# Current_Sensor.net
KiCad netlist of a schematic drawn in Altium Designer
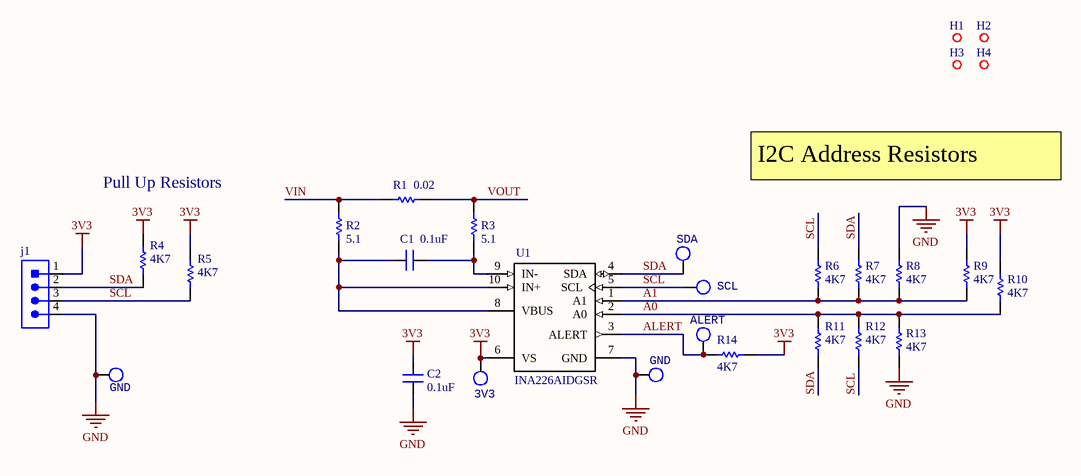
[diagram p0: Current Sensor.SchDoc]

(export (version "E")
  (design (tool "Eeschema 10.0.6"))
  (components
    (comp (ref "C1")
      (value "0.1uF")
      (footprint "CAPC2012X140N")
      (description "CAP CER 0.1UF 50V X7R 0805")
      (fields (field (name "TOLERANCE") "10%") (field (name "Comment") "CAP_0.1uF_50V_0805"))
      (libsource (lib "UWRT_Schematic_Library_2020") (part "CAP_0.1uF_50V_0805"))
    )
    (comp (ref "C2")
      (value "0.1uF")
      (footprint "CAPC2012X140N")
      (description "CAP CER 0.1UF 50V X7R 0805")
      (fields (field (name "TOLERANCE") "10%") (field (name "Comment") "CAP_0.1uF_50V_0805"))
      (libsource (lib "UWRT_Schematic_Library_2020") (part "CAP_0.1uF_50V_0805"))
    )
    (comp (ref "H1")
      (value "MOUNTING_HOLES")
      (footprint "MOUNTING_HOLE")
      (description "6cm x 6cm")
      (libsource (lib "UWRT_Schematic_Library_2020") (part "MOUNTING_HOLES"))
    )
    (comp (ref "H2")
      (value "MOUNTING_HOLES")
      (footprint "MOUNTING_HOLE")
      (description "6cm x 6cm")
      (libsource (lib "UWRT_Schematic_Library_2020") (part "MOUNTING_HOLES"))
    )
    (comp (ref "H3")
      (value "MOUNTING_HOLES")
      (footprint "MOUNTING_HOLE")
      (description "6cm x 6cm")
      (libsource (lib "UWRT_Schematic_Library_2020") (part "MOUNTING_HOLES"))
    )
    (comp (ref "H4")
      (value "MOUNTING_HOLES")
      (footprint "MOUNTING_HOLE")
      (description "6cm x 6cm")
      (libsource (lib "UWRT_Schematic_Library_2020") (part "MOUNTING_HOLES"))
    )
    (comp (ref "j1")
      (value "CON_4M_TERM")
      (footprint "UWRT_Footprint_Library_2020:1935187")
      (description "TERM BLK 4POS SIDE ENTRY 5MM PCB")
      (fields (field (name "VOLTAGE") "300V"))
      (libsource (lib "UWRT_Schematic_Library_2020") (part "CON_4M_TERM"))
    )
    (comp (ref "R1")
      (value "0.02")
      (footprint "RESC6532X75N")
      (description "RES 0.02 OHM 1% 3W 2512")
      (fields (field (name "Comment") "RES_20m_2512"))
      (libsource (lib "UWRT_Schematic_Library_2020") (part "RES_20m_2512"))
    )
    (comp (ref "R2")
      (value "5.1")
      (footprint "RESC2013X70X40LL20T20")
      (description "RES SMD 5.1 OHM 5% 1/8W 0805")
      (fields (field (name "PART NUMBER") "ERJ-6GEYJ5R1V") (field (name "MANUFACTURER") "Panasonic"))
      (libsource (lib "UWRT_Schematic_Library_2020") (part "RES_5.1_0805"))
    )
    (comp (ref "R3")
      (value "5.1")
      (footprint "RESC2013X70X40LL20T20")
      (description "RES SMD 5.1 OHM 5% 1/8W 0805")
      (fields (field (name "PART NUMBER") "ERJ-6GEYJ5R1V") (field (name "MANUFACTURER") "Panasonic"))
      (libsource (lib "UWRT_Schematic_Library_2020") (part "RES_5.1_0805"))
    )
    (comp (ref "R4")
      (value "4K7")
      (footprint "RESC2012X60N")
      (description "RES SMD 4.7K OHM 5% 1/8W 0805")
      (fields (field (name "TOLERANCE") "5%") (field (name "Comment") "RES_4K7_0805"))
      (libsource (lib "UWRT_Schematic_Library_2020") (part "RES_4K7_0805"))
    )
    (comp (ref "R5")
      (value "4K7")
      (footprint "RESC2012X60N")
      (description "RES SMD 4.7K OHM 5% 1/8W 0805")
      (fields (field (name "TOLERANCE") "5%") (field (name "Comment") "RES_4K7_0805"))
      (libsource (lib "UWRT_Schematic_Library_2020") (part "RES_4K7_0805"))
    )
    (comp (ref "R6")
      (value "4K7")
      (footprint "RESC2012X60N")
      (description "RES SMD 4.7K OHM 5% 1/8W 0805")
      (fields (field (name "TOLERANCE") "5%") (field (name "Comment") "RES_4K7_0805"))
      (libsource (lib "UWRT_Schematic_Library_2020") (part "RES_4K7_0805"))
    )
    (comp (ref "R7")
      (value "4K7")
      (footprint "RESC2012X60N")
      (description "RES SMD 4.7K OHM 5% 1/8W 0805")
      (fields (field (name "TOLERANCE") "5%") (field (name "Comment") "RES_4K7_0805"))
      (libsource (lib "UWRT_Schematic_Library_2020") (part "RES_4K7_0805"))
    )
    (comp (ref "R8")
      (value "4K7")
      (footprint "RESC2012X60N")
      (description "RES SMD 4.7K OHM 5% 1/8W 0805")
      (fields (field (name "TOLERANCE") "5%") (field (name "Comment") "RES_4K7_0805"))
      (libsource (lib "UWRT_Schematic_Library_2020") (part "RES_4K7_0805"))
    )
    (comp (ref "R9")
      (value "4K7")
      (footprint "RESC2012X60N")
      (description "RES SMD 4.7K OHM 5% 1/8W 0805")
      (fields (field (name "TOLERANCE") "5%") (field (name "Comment") "RES_4K7_0805"))
      (libsource (lib "UWRT_Schematic_Library_2020") (part "RES_4K7_0805"))
    )
    (comp (ref "R10")
      (value "4K7")
      (footprint "RESC2012X60N")
      (description "RES SMD 4.7K OHM 5% 1/8W 0805")
      (fields (field (name "TOLERANCE") "5%") (field (name "Comment") "RES_4K7_0805"))
      (libsource (lib "UWRT_Schematic_Library_2020") (part "RES_4K7_0805"))
    )
    (comp (ref "R11")
      (value "4K7")
      (footprint "RESC2012X60N")
      (description "RES SMD 4.7K OHM 5% 1/8W 0805")
      (fields (field (name "TOLERANCE") "5%") (field (name "Comment") "RES_4K7_0805"))
      (libsource (lib "UWRT_Schematic_Library_2020") (part "RES_4K7_0805"))
    )
    (comp (ref "R12")
      (value "4K7")
      (footprint "RESC2012X60N")
      (description "RES SMD 4.7K OHM 5% 1/8W 0805")
      (fields (field (name "TOLERANCE") "5%") (field (name "Comment") "RES_4K7_0805"))
      (libsource (lib "UWRT_Schematic_Library_2020") (part "RES_4K7_0805"))
    )
    (comp (ref "R13")
      (value "4K7")
      (footprint "RESC2012X60N")
      (description "RES SMD 4.7K OHM 5% 1/8W 0805")
      (fields (field (name "TOLERANCE") "5%") (field (name "Comment") "RES_4K7_0805"))
      (libsource (lib "UWRT_Schematic_Library_2020") (part "RES_4K7_0805"))
    )
    (comp (ref "R14")
      (value "4K7")
      (footprint "RESC2012X60N")
      (description "RES SMD 4.7K OHM 5% 1/8W 0805")
      (fields (field (name "TOLERANCE") "5%") (field (name "Comment") "RES_4K7_0805"))
      (libsource (lib "UWRT_Schematic_Library_2020") (part "RES_4K7_0805"))
    )
    (comp (ref "TP1")
      (value "SDA")
      (footprint "TESTPOINT_LOOP")
      (description "Loop testpoint through-hole pad")
      (fields (field (name "MANUFACTURER") "Keystone Electronics"))
      (libsource (lib "UWRT_Schematic_Library_2020") (part "TESTPOINT_LOOP"))
    )
    (comp (ref "TP2")
      (value "SCL")
      (footprint "TESTPOINT_LOOP")
      (description "Loop testpoint through-hole pad")
      (fields (field (name "MANUFACTURER") "Keystone Electronics"))
      (libsource (lib "UWRT_Schematic_Library_2020") (part "TESTPOINT_LOOP"))
    )
    (comp (ref "TP3")
      (value "ALERT")
      (footprint "TESTPOINT_LOOP")
      (description "Loop testpoint through-hole pad")
      (fields (field (name "MANUFACTURER") "Keystone Electronics"))
      (libsource (lib "UWRT_Schematic_Library_2020") (part "TESTPOINT_LOOP"))
    )
    (comp (ref "TP4")
      (value "GND")
      (footprint "TESTPOINT_LOOP")
      (description "Loop testpoint through-hole pad")
      (fields (field (name "MANUFACTURER") "Keystone Electronics"))
      (libsource (lib "UWRT_Schematic_Library_2020") (part "TESTPOINT_LOOP"))
    )
    (comp (ref "TP5")
      (value "3V3")
      (footprint "TESTPOINT_LOOP")
      (description "Loop testpoint through-hole pad")
      (fields (field (name "MANUFACTURER") "Keystone Electronics"))
      (libsource (lib "UWRT_Schematic_Library_2020") (part "TESTPOINT_LOOP"))
    )
    (comp (ref "TP6")
      (value "GND")
      (footprint "TESTPOINT_LOOP")
      (description "Loop testpoint through-hole pad")
      (libsource (lib "UWRT_Schematic_Library_2020") (part "TESTPOINT_LOOP"))
    )
    (comp (ref "U1")
      (value "INA226AIDGSR")
      (footprint "INA226AIDGSR")
      (description "IC MONITOR PWR/CURR BIDIR 10MSOP")
      (fields (field (name "MF") "Texas Instruments"))
      (libsource (lib "UWRT_Schematic_Library_2020") (part "INA226AIDGSR"))
    )
  )
  (nets
    (net (code "1") (name "/A0") (class "Default")
      (node (ref "R10") (pin "1") (pinfunction "1_1") (pintype "passive"))
      (node (ref "R11") (pin "1") (pinfunction "1_1") (pintype "passive"))
      (node (ref "R12") (pin "1") (pinfunction "1_1") (pintype "passive"))
      (node (ref "R13") (pin "1") (pinfunction "1_1") (pintype "passive"))
      (node (ref "U1") (pin "2") (pinfunction "A0_2") (pintype "input"))
    )
    (net (code "2") (name "/A1") (class "Default")
      (node (ref "R6") (pin "1") (pinfunction "1_1") (pintype "passive"))
      (node (ref "R7") (pin "1") (pinfunction "1_1") (pintype "passive"))
      (node (ref "R8") (pin "1") (pinfunction "1_1") (pintype "passive"))
      (node (ref "R9") (pin "1") (pinfunction "1_1") (pintype "passive"))
      (node (ref "U1") (pin "1") (pinfunction "A1_1") (pintype "input"))
    )
    (net (code "3") (name "/ALERT") (class "Default")
      (node (ref "R14") (pin "1") (pinfunction "1_1") (pintype "passive"))
      (node (ref "TP3") (pin "1") (pintype "passive"))
      (node (ref "U1") (pin "3") (pinfunction "ALERT_3") (pintype "output"))
    )
    (net (code "4") (name "/SCL") (class "Default")
      (node (ref "R12") (pin "2") (pinfunction "2_2") (pintype "passive"))
      (node (ref "R5") (pin "2") (pinfunction "2_2") (pintype "passive"))
      (node (ref "R6") (pin "2") (pinfunction "2_2") (pintype "passive"))
      (node (ref "TP2") (pin "1") (pintype "passive"))
      (node (ref "U1") (pin "5") (pinfunction "SCL_5") (pintype "input"))
      (node (ref "j1") (pin "3") (pinfunction "3_3") (pintype "passive"))
    )
    (net (code "5") (name "/SDA") (class "Default")
      (node (ref "R11") (pin "2") (pinfunction "2_2") (pintype "passive"))
      (node (ref "R4") (pin "2") (pinfunction "2_2") (pintype "passive"))
      (node (ref "R7") (pin "2") (pinfunction "2_2") (pintype "passive"))
      (node (ref "TP1") (pin "1") (pintype "passive"))
      (node (ref "U1") (pin "4") (pinfunction "SDA_4") (pintype "bidirectional"))
      (node (ref "j1") (pin "2") (pinfunction "2_2") (pintype "passive"))
    )
    (net (code "6") (name "/VIN") (class "Default")
      (node (ref "R1") (pin "1") (pinfunction "1_1") (pintype "passive"))
      (node (ref "R2") (pin "2") (pinfunction "2_2") (pintype "passive"))
    )
    (net (code "7") (name "/VOUT") (class "Default")
      (node (ref "R1") (pin "2") (pinfunction "2_2") (pintype "passive"))
      (node (ref "R3") (pin "2") (pinfunction "2_2") (pintype "passive"))
    )
    (net (code "8") (name "3V3") (class "Default")
      (node (ref "C2") (pin "2") (pinfunction "2_2") (pintype "passive"))
      (node (ref "R10") (pin "2") (pinfunction "2_2") (pintype "passive"))
      (node (ref "R14") (pin "2") (pinfunction "2_2") (pintype "passive"))
      (node (ref "R4") (pin "1") (pinfunction "1_1") (pintype "passive"))
      (node (ref "R5") (pin "1") (pinfunction "1_1") (pintype "passive"))
      (node (ref "R9") (pin "2") (pinfunction "2_2") (pintype "passive"))
      (node (ref "TP5") (pin "1") (pintype "passive"))
      (node (ref "U1") (pin "6") (pinfunction "VS_6") (pintype "power_in"))
      (node (ref "j1") (pin "1") (pinfunction "1_1") (pintype "passive"))
    )
    (net (code "9") (name "GND") (class "Default")
      (node (ref "C2") (pin "1") (pinfunction "1_1") (pintype "passive"))
      (node (ref "R13") (pin "2") (pinfunction "2_2") (pintype "passive"))
      (node (ref "R8") (pin "2") (pinfunction "2_2") (pintype "passive"))
      (node (ref "TP4") (pin "1") (pintype "passive"))
      (node (ref "TP6") (pin "1") (pintype "passive"))
      (node (ref "U1") (pin "7") (pinfunction "GND_7") (pintype "power_in"))
      (node (ref "j1") (pin "4") (pinfunction "4_4") (pintype "passive"))
    )
    (net (code "10") (name "Net-(U1-IN+)") (class "Default")
      (node (ref "C1") (pin "1") (pinfunction "1_1") (pintype "passive"))
      (node (ref "R2") (pin "1") (pinfunction "1_1") (pintype "passive"))
      (node (ref "U1") (pin "10") (pinfunction "IN+_10") (pintype "input"))
      (node (ref "U1") (pin "8") (pinfunction "VBUS_8") (pintype "power_in"))
    )
    (net (code "11") (name "Net-(U1-IN-)") (class "Default")
      (node (ref "C1") (pin "2") (pinfunction "2_2") (pintype "passive"))
      (node (ref "R3") (pin "1") (pinfunction "1_1") (pintype "passive"))
      (node (ref "U1") (pin "9") (pinfunction "IN-_9") (pintype "input"))
    )
  )
)
